# Adafruit_VCNL4010.net
KiCad netlist of a schematic drawn in EAGLE
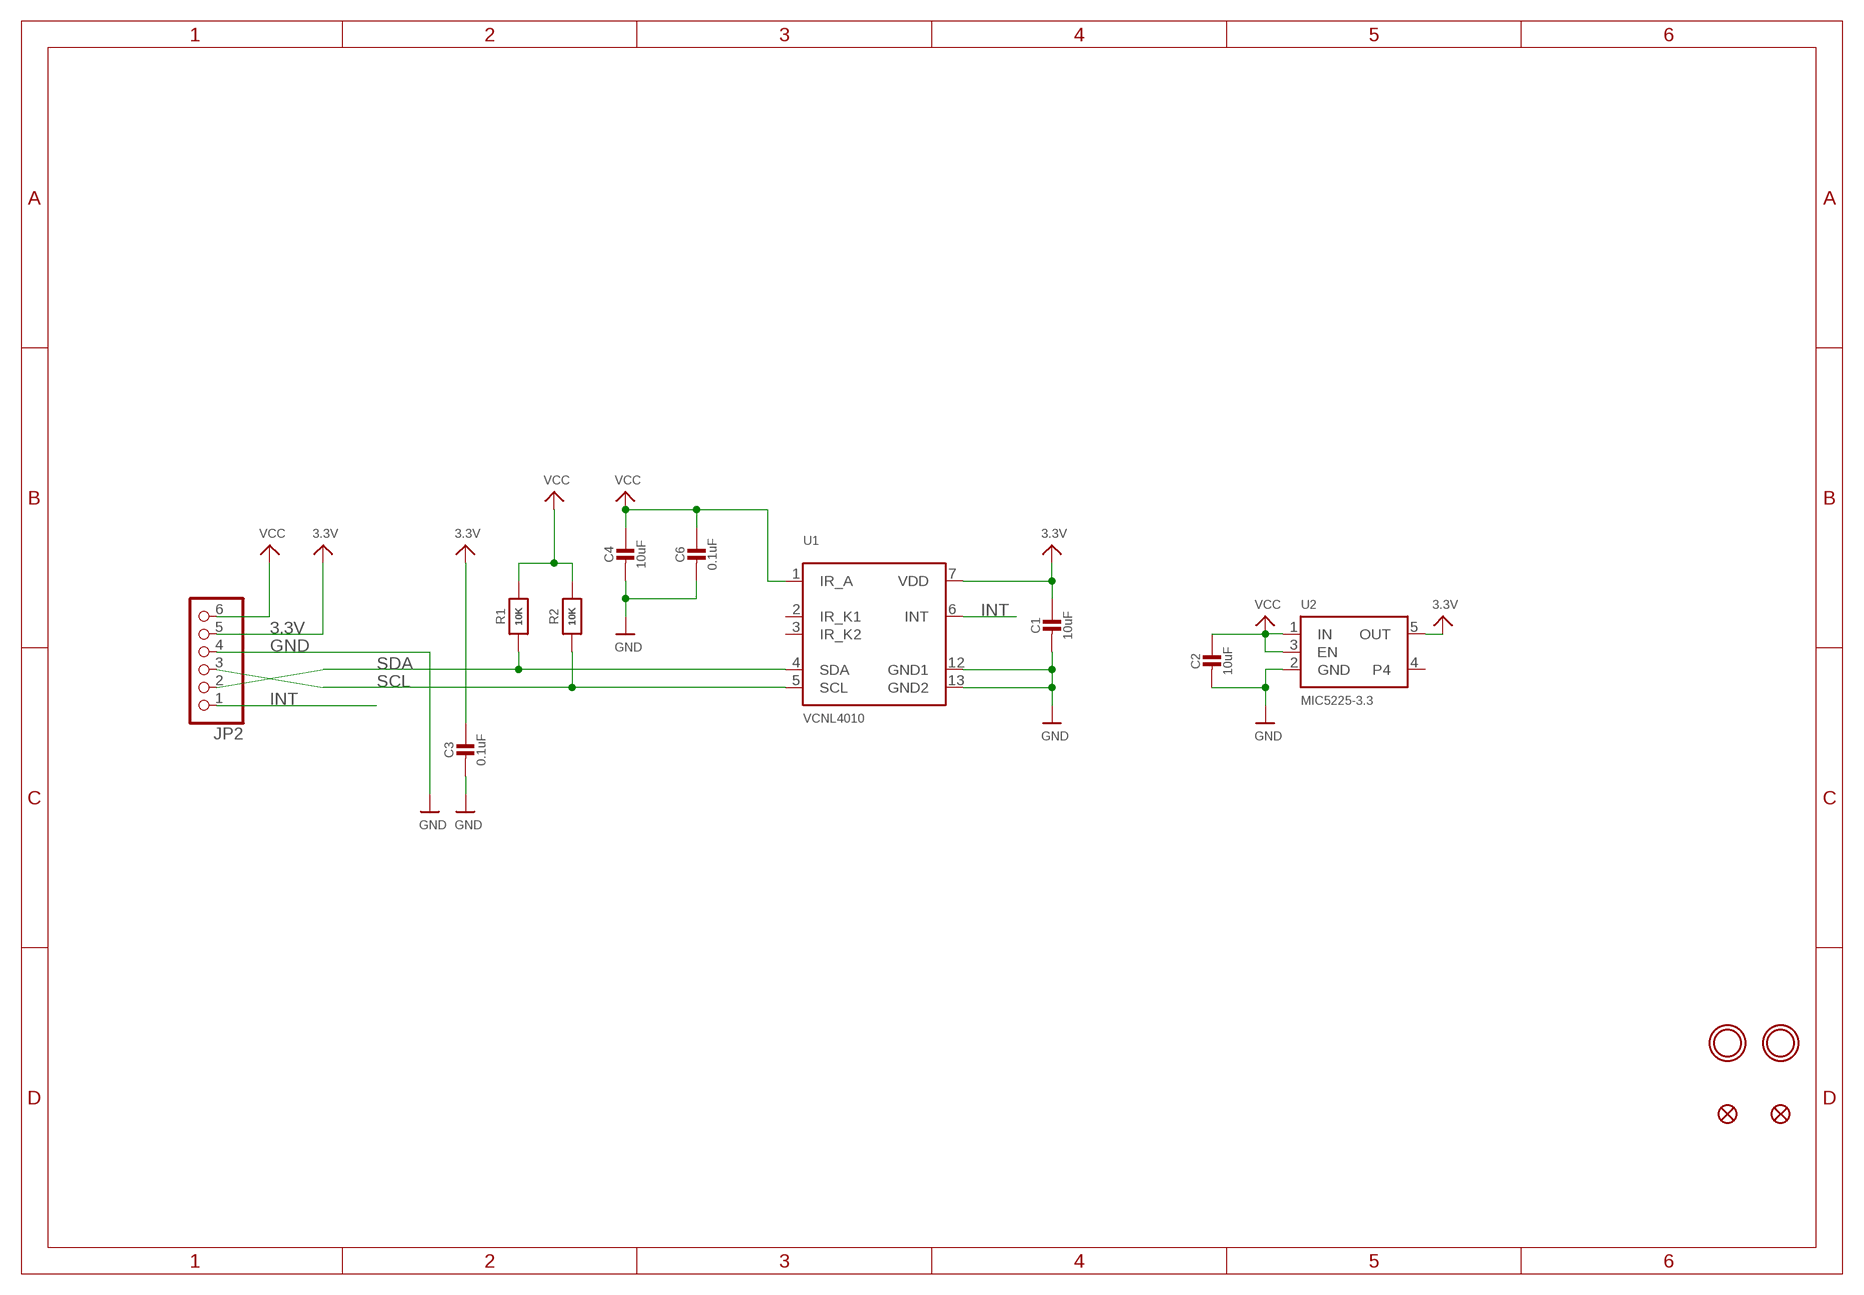
[diagram p0: schematic, sheet 1]

(export (version "E")
  (design (tool "Eeschema 10.0.6"))
  (components
    (comp (ref "C1")
      (value "10uF")
      (footprint "eagle-import:0805-NO")
      (libsource (lib "eagle-import") (part "CAP_CERAMIC0805-NOOUTLINE"))
    )
    (comp (ref "C2")
      (value "10uF")
      (footprint "eagle-import:0805-NO")
      (libsource (lib "eagle-import") (part "CAP_CERAMIC0805-NOOUTLINE"))
    )
    (comp (ref "C3")
      (value "0.1uF")
      (footprint "eagle-import:0805-NO")
      (libsource (lib "eagle-import") (part "CAP_CERAMIC0805-NOOUTLINE"))
    )
    (comp (ref "C4")
      (value "10uF")
      (footprint "eagle-import:0805-NO")
      (libsource (lib "eagle-import") (part "CAP_CERAMIC0805-NOOUTLINE"))
    )
    (comp (ref "C6")
      (value "0.1uF")
      (footprint "eagle-import:0805-NO")
      (libsource (lib "eagle-import") (part "CAP_CERAMIC0805-NOOUTLINE"))
    )
    (comp (ref "JP2")
      (value "HEADER-1X676MIL")
      (footprint "eagle-import:1X06_ROUND_76")
      (libsource (lib "eagle-import") (part "HEADER-1X676MIL"))
    )
    (comp (ref "R1")
      (value "10K")
      (footprint "eagle-import:0805-NO")
      (libsource (lib "eagle-import") (part "RESISTOR0805_NOOUTLINE"))
    )
    (comp (ref "R2")
      (value "10K")
      (footprint "eagle-import:0805-NO")
      (libsource (lib "eagle-import") (part "RESISTOR0805_NOOUTLINE"))
    )
    (comp (ref "U$5")
      (value "MOUNTINGHOLE2.5")
      (footprint "eagle-import:MOUNTINGHOLE_2.5_PLATED")
      (libsource (lib "eagle-import") (part "MOUNTINGHOLE2.5"))
    )
    (comp (ref "U$6")
      (value "MOUNTINGHOLE2.5")
      (footprint "eagle-import:MOUNTINGHOLE_2.5_PLATED")
      (libsource (lib "eagle-import") (part "MOUNTINGHOLE2.5"))
    )
    (comp (ref "U$7")
      (value "FIDUCIAL\"\"")
      (footprint "eagle-import:FIDUCIAL_1MM")
      (libsource (lib "eagle-import") (part "FIDUCIAL{dblquote}{dblquote}"))
    )
    (comp (ref "U$8")
      (value "FIDUCIAL\"\"")
      (footprint "eagle-import:FIDUCIAL_1MM")
      (libsource (lib "eagle-import") (part "FIDUCIAL{dblquote}{dblquote}"))
    )
    (comp (ref "U1")
      (value "VCNL4010")
      (footprint "eagle-import:VCNL4010")
      (libsource (lib "eagle-import") (part "VCNL4010"))
    )
    (comp (ref "U2")
      (value "MIC5225-3.3")
      (footprint "eagle-import:SOT23-5")
      (libsource (lib "eagle-import") (part "VREG_SOT23-5"))
    )
  )
  (nets
    (net (code "1") (name "/INT") (class "Default")
      (node (ref "JP2") (pin "1") (pinfunction "1_1") (pintype "passive"))
      (node (ref "U1") (pin "6") (pinfunction "INT_6") (pintype "output"))
    )
    (net (code "2") (name "/SCL") (class "Default")
      (node (ref "JP2") (pin "3") (pinfunction "3_3") (pintype "passive"))
      (node (ref "R2") (pin "1") (pinfunction "1_1") (pintype "passive"))
      (node (ref "U1") (pin "5") (pinfunction "SCL_5") (pintype "open_collector"))
    )
    (net (code "3") (name "/SDA") (class "Default")
      (node (ref "JP2") (pin "2") (pinfunction "2_2") (pintype "passive"))
      (node (ref "R1") (pin "1") (pinfunction "1_1") (pintype "passive"))
      (node (ref "U1") (pin "4") (pinfunction "SDA_4") (pintype "open_collector"))
    )
    (net (code "4") (name "3.3V") (class "Default")
      (node (ref "C1") (pin "1") (pinfunction "1_1") (pintype "passive"))
      (node (ref "C3") (pin "1") (pinfunction "1_1") (pintype "passive"))
      (node (ref "JP2") (pin "5") (pinfunction "5_5") (pintype "passive"))
      (node (ref "U1") (pin "7") (pinfunction "VDD_7") (pintype "power_in"))
      (node (ref "U2") (pin "5") (pinfunction "OUT_5") (pintype "power_in"))
    )
    (net (code "5") (name "GND") (class "Default")
      (node (ref "C1") (pin "2") (pinfunction "2_2") (pintype "passive"))
      (node (ref "C2") (pin "2") (pinfunction "2_2") (pintype "passive"))
      (node (ref "C3") (pin "2") (pinfunction "2_2") (pintype "passive"))
      (node (ref "C4") (pin "2") (pinfunction "2_2") (pintype "passive"))
      (node (ref "C6") (pin "2") (pinfunction "2_2") (pintype "passive"))
      (node (ref "JP2") (pin "4") (pinfunction "4_4") (pintype "passive"))
      (node (ref "U1") (pin "12") (pinfunction "GND1_12") (pintype "power_in"))
      (node (ref "U1") (pin "13") (pinfunction "GND2_13") (pintype "power_in"))
      (node (ref "U2") (pin "2") (pinfunction "GND_2") (pintype "power_in"))
    )
    (net (code "6") (name "VCC") (class "Default")
      (node (ref "C2") (pin "1") (pinfunction "1_1") (pintype "passive"))
      (node (ref "C4") (pin "1") (pinfunction "1_1") (pintype "passive"))
      (node (ref "C6") (pin "1") (pinfunction "1_1") (pintype "passive"))
      (node (ref "JP2") (pin "6") (pinfunction "6_6") (pintype "passive"))
      (node (ref "R1") (pin "2") (pinfunction "2_2") (pintype "passive"))
      (node (ref "R2") (pin "2") (pinfunction "2_2") (pintype "passive"))
      (node (ref "U1") (pin "1") (pinfunction "IR_A_1") (pintype "bidirectional"))
      (node (ref "U2") (pin "1") (pinfunction "IN_1") (pintype "power_in"))
      (node (ref "U2") (pin "3") (pinfunction "EN_3") (pintype "input"))
    )
    (net (code "7") (name "unconnected-(U1-IR_K1-Pad2)") (class "Default")
      (node (ref "U1") (pin "2") (pinfunction "IR_K1_2") (pintype "bidirectional"))
    )
    (net (code "8") (name "unconnected-(U1-IR_K2-Pad3)") (class "Default")
      (node (ref "U1") (pin "3") (pinfunction "IR_K2_3") (pintype "bidirectional"))
    )
    (net (code "9") (name "unconnected-(U2-P4-Pad4)") (class "Default")
      (node (ref "U2") (pin "4") (pinfunction "P4_4") (pintype "bidirectional"))
    )
  )
)
